# main.net
KiCad netlist of a schematic drawn in EAGLE
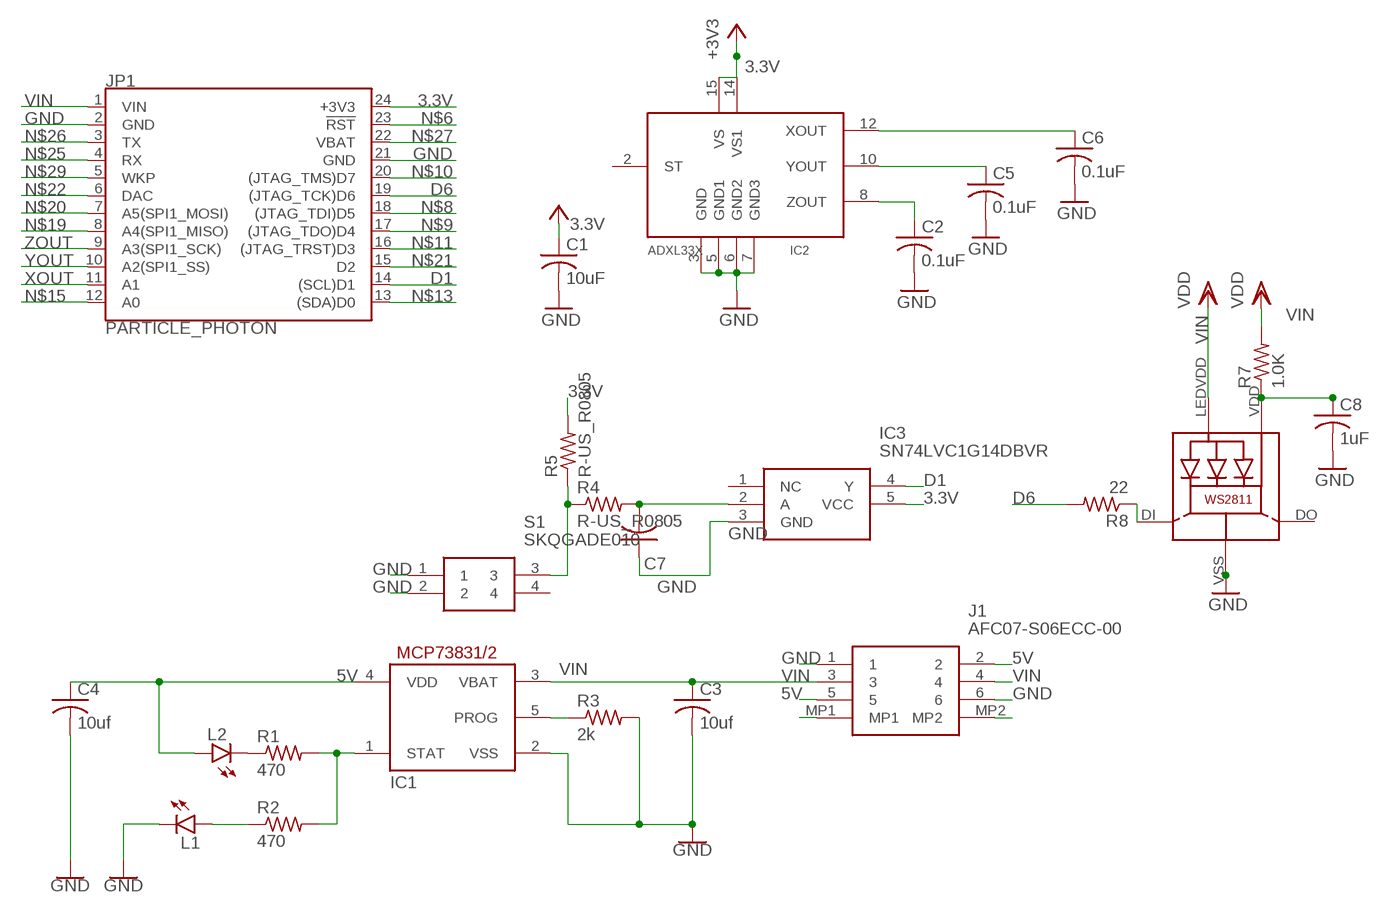
[diagram p0: schematic, sheet 1]

(export (version "E")
  (design (tool "Eeschema 10.0.6"))
  (components
    (comp (ref "C1")
      (value "10uF")
      (footprint "eagle-import:ADAFRUIT_C0805K")
      (libsource (lib "eagle-import") (part "ADAFRUIT_C-USC0805K"))
    )
    (comp (ref "C2")
      (value "0.1uF")
      (footprint "eagle-import:ADAFRUIT_C0805K")
      (libsource (lib "eagle-import") (part "ADAFRUIT_C-USC0805K"))
    )
    (comp (ref "C3")
      (value "10uf")
      (footprint "eagle-import:ADAFRUIT_C0805K")
      (libsource (lib "eagle-import") (part "ADAFRUIT_C-USC0805K"))
    )
    (comp (ref "C4")
      (value "10uf")
      (footprint "eagle-import:ADAFRUIT_C0805K")
      (libsource (lib "eagle-import") (part "ADAFRUIT_C-USC0805K"))
    )
    (comp (ref "C5")
      (value "0.1uF")
      (footprint "eagle-import:ADAFRUIT_C0805K")
      (libsource (lib "eagle-import") (part "ADAFRUIT_C-USC0805K"))
    )
    (comp (ref "C6")
      (value "0.1uF")
      (footprint "eagle-import:ADAFRUIT_C0805K")
      (libsource (lib "eagle-import") (part "ADAFRUIT_C-USC0805K"))
    )
    (comp (ref "C7")
      (value "ADAFRUIT_C-USC0805K")
      (footprint "eagle-import:ADAFRUIT_C0805K")
      (libsource (lib "eagle-import") (part "ADAFRUIT_C-USC0805K"))
    )
    (comp (ref "C8")
      (value "1uF")
      (footprint "eagle-import:ADAFRUIT_C0805K")
      (libsource (lib "eagle-import") (part "ADAFRUIT_C-USC0805K"))
    )
    (comp (ref "IC1")
      (value "MCP73831/OT")
      (footprint "eagle-import:SOT23-5L")
      (libsource (lib "eagle-import") (part "MCP73831/OT"))
    )
    (comp (ref "IC2")
      (value "ADXL33X")
      (footprint "eagle-import:16LCSP")
      (libsource (lib "eagle-import") (part "ADXL33X"))
    )
    (comp (ref "IC3")
      (value "SN74LVC1G14DBVR")
      (footprint "eagle-import:SOT95P280X145-5N")
      (fields (field (name "MOUSER_PART_NUMBER") "595-SN74LVC1G14DBVR"))
      (libsource (lib "eagle-import") (part "SN74LVC1G14DBVR"))
    )
    (comp (ref "J1")
      (value "AFC07-S06ECC-00")
      (footprint "eagle-import:AFC07S06ECC00")
      (libsource (lib "eagle-import") (part "AFC07-S06ECC-00"))
    )
    (comp (ref "JP1")
      (value "PARTICLE_PHOTON")
      (footprint "eagle-import:PARTICLE_PHOTON")
      (libsource (lib "eagle-import") (part "PARTICLE_PHOTON"))
    )
    (comp (ref "L1")
      (value "green")
      (footprint "eagle-import:FKIT-LED-1206")
      (libsource (lib "eagle-import") (part "LED-FKIT-1206"))
    )
    (comp (ref "L2")
      (value "blue")
      (footprint "eagle-import:FKIT-LED-1206")
      (libsource (lib "eagle-import") (part "LED-FKIT-1206"))
    )
    (comp (ref "LED1")
      (value "WS28115050")
      (footprint "eagle-import:WS28115050")
      (libsource (lib "eagle-import") (part "WS28115050"))
    )
    (comp (ref "R1")
      (value "470")
      (footprint "eagle-import:R0805")
      (libsource (lib "eagle-import") (part "R-US_R0805"))
    )
    (comp (ref "R2")
      (value "470")
      (footprint "eagle-import:R0805")
      (libsource (lib "eagle-import") (part "R-US_R0805"))
    )
    (comp (ref "R3")
      (value "2k")
      (footprint "eagle-import:R0805")
      (libsource (lib "eagle-import") (part "R-US_R0805"))
    )
    (comp (ref "R4")
      (value "R-US_R0805")
      (footprint "eagle-import:R0805")
      (libsource (lib "eagle-import") (part "R-US_R0805"))
    )
    (comp (ref "R5")
      (value "R-US_R0805")
      (footprint "eagle-import:R0805")
      (libsource (lib "eagle-import") (part "R-US_R0805"))
    )
    (comp (ref "R7")
      (value "1.0K")
      (footprint "eagle-import:R0805")
      (libsource (lib "eagle-import") (part "R-US_R0805"))
    )
    (comp (ref "R8")
      (value "22")
      (footprint "eagle-import:R0805")
      (libsource (lib "eagle-import") (part "R-US_R0805"))
    )
    (comp (ref "S1")
      (value "SKQGADE010")
      (footprint "eagle-import:SKQGAKE010")
      (fields (field (name "MOUSER_PART_NUMBER") "688-SKQGAD") (field (name "RS_PART_NUMBER") "7582067"))
      (libsource (lib "eagle-import") (part "SKQGADE010"))
    )
  )
  (nets
    (net (code "1") (name "+3V3") (class "Default")
      (node (ref "C1") (pin "1") (pinfunction "1_1") (pintype "passive"))
      (node (ref "IC2") (pin "14") (pinfunction "VS1_14") (pintype "power_in"))
      (node (ref "IC2") (pin "15") (pinfunction "VS_15") (pintype "power_in"))
      (node (ref "IC3") (pin "5") (pinfunction "VCC_5") (pintype "bidirectional"))
      (node (ref "JP1") (pin "24") (pinfunction "+3V3_24") (pintype "power_in"))
      (node (ref "R5") (pin "2") (pinfunction "2_2") (pintype "passive"))
    )
    (net (code "2") (name "/5V") (class "Default")
      (node (ref "C4") (pin "1") (pinfunction "1_1") (pintype "passive"))
      (node (ref "IC1") (pin "4") (pinfunction "VDD_4") (pintype "power_in"))
      (node (ref "J1") (pin "2") (pinfunction "2_2") (pintype "bidirectional"))
      (node (ref "J1") (pin "5") (pinfunction "5_5") (pintype "bidirectional"))
      (node (ref "L2") (pin "A") (pinfunction "A_A") (pintype "passive"))
    )
    (net (code "3") (name "/D1") (class "Default")
      (node (ref "IC3") (pin "4") (pinfunction "Y_4") (pintype "bidirectional"))
      (node (ref "JP1") (pin "14") (pinfunction "(SCL)D1_14") (pintype "bidirectional"))
    )
    (net (code "4") (name "/D6") (class "Default")
      (node (ref "JP1") (pin "19") (pinfunction "(JTAG_TCK)D6_19") (pintype "bidirectional"))
      (node (ref "R8") (pin "2") (pinfunction "2_2") (pintype "passive"))
    )
    (net (code "5") (name "/N$6") (class "Default")
      (node (ref "JP1") (pin "23") (pinfunction "~{RST}_23") (pintype "bidirectional"))
    )
    (net (code "6") (name "/N$8") (class "Default")
      (node (ref "JP1") (pin "18") (pinfunction "(JTAG_TDI)D5_18") (pintype "bidirectional"))
    )
    (net (code "7") (name "/N$9") (class "Default")
      (node (ref "JP1") (pin "17") (pinfunction "(JTAG_TDO)D4_17") (pintype "bidirectional"))
    )
    (net (code "8") (name "/N$10") (class "Default")
      (node (ref "JP1") (pin "20") (pinfunction "(JTAG_TMS)D7_20") (pintype "bidirectional"))
    )
    (net (code "9") (name "/N$11") (class "Default")
      (node (ref "JP1") (pin "16") (pinfunction "(JTAG_TRST)D3_16") (pintype "bidirectional"))
    )
    (net (code "10") (name "/N$13") (class "Default")
      (node (ref "JP1") (pin "13") (pinfunction "(SDA)D0_13") (pintype "bidirectional"))
    )
    (net (code "11") (name "/N$15") (class "Default")
      (node (ref "JP1") (pin "12") (pinfunction "A0_12") (pintype "bidirectional"))
    )
    (net (code "12") (name "/N$19") (class "Default")
      (node (ref "JP1") (pin "8") (pinfunction "A4(SPI1_MISO)_8") (pintype "bidirectional"))
    )
    (net (code "13") (name "/N$20") (class "Default")
      (node (ref "JP1") (pin "7") (pinfunction "A5(SPI1_MOSI)_7") (pintype "bidirectional"))
    )
    (net (code "14") (name "/N$21") (class "Default")
      (node (ref "JP1") (pin "15") (pinfunction "D2_15") (pintype "bidirectional"))
    )
    (net (code "15") (name "/N$22") (class "Default")
      (node (ref "JP1") (pin "6") (pinfunction "DAC_6") (pintype "bidirectional"))
    )
    (net (code "16") (name "/N$25") (class "Default")
      (node (ref "JP1") (pin "4") (pinfunction "RX_4") (pintype "bidirectional"))
    )
    (net (code "17") (name "/N$26") (class "Default")
      (node (ref "JP1") (pin "3") (pinfunction "TX_3") (pintype "bidirectional"))
    )
    (net (code "18") (name "/N$27") (class "Default")
      (node (ref "JP1") (pin "22") (pinfunction "VBAT_22") (pintype "power_in"))
    )
    (net (code "19") (name "/N$29") (class "Default")
      (node (ref "JP1") (pin "5") (pinfunction "WKP_5") (pintype "bidirectional"))
    )
    (net (code "20") (name "/XOUT") (class "Default")
      (node (ref "C6") (pin "1") (pinfunction "1_1") (pintype "passive"))
      (node (ref "IC2") (pin "12") (pinfunction "XOUT_12") (pintype "output"))
      (node (ref "JP1") (pin "11") (pinfunction "A1_11") (pintype "bidirectional"))
    )
    (net (code "21") (name "/YOUT") (class "Default")
      (node (ref "C5") (pin "1") (pinfunction "1_1") (pintype "passive"))
      (node (ref "IC2") (pin "10") (pinfunction "YOUT_10") (pintype "output"))
      (node (ref "JP1") (pin "10") (pinfunction "A2(SPI1_SS)_10") (pintype "bidirectional"))
    )
    (net (code "22") (name "/ZOUT") (class "Default")
      (node (ref "C2") (pin "1") (pinfunction "1_1") (pintype "passive"))
      (node (ref "IC2") (pin "8") (pinfunction "ZOUT_8") (pintype "output"))
      (node (ref "JP1") (pin "9") (pinfunction "A3(SPI1_SCK)_9") (pintype "bidirectional"))
    )
    (net (code "23") (name "GND") (class "Default")
      (node (ref "C1") (pin "2") (pinfunction "2_2") (pintype "passive"))
      (node (ref "C2") (pin "2") (pinfunction "2_2") (pintype "passive"))
      (node (ref "C3") (pin "2") (pinfunction "2_2") (pintype "passive"))
      (node (ref "C4") (pin "2") (pinfunction "2_2") (pintype "passive"))
      (node (ref "C5") (pin "2") (pinfunction "2_2") (pintype "passive"))
      (node (ref "C6") (pin "2") (pinfunction "2_2") (pintype "passive"))
      (node (ref "C7") (pin "1") (pinfunction "1_1") (pintype "passive"))
      (node (ref "C8") (pin "2") (pinfunction "2_2") (pintype "passive"))
      (node (ref "IC1") (pin "2") (pinfunction "VSS_2") (pintype "power_in"))
      (node (ref "IC2") (pin "3") (pinfunction "GND_3") (pintype "power_in"))
      (node (ref "IC2") (pin "5") (pinfunction "GND1_5") (pintype "power_in"))
      (node (ref "IC2") (pin "6") (pinfunction "GND2_6") (pintype "power_in"))
      (node (ref "IC2") (pin "7") (pinfunction "GND3_7") (pintype "power_in"))
      (node (ref "IC3") (pin "3") (pinfunction "GND_3") (pintype "bidirectional"))
      (node (ref "J1") (pin "1") (pinfunction "1_1") (pintype "bidirectional"))
      (node (ref "J1") (pin "6") (pinfunction "6_6") (pintype "bidirectional"))
      (node (ref "JP1") (pin "2") (pinfunction "GND_2") (pintype "power_in"))
      (node (ref "JP1") (pin "21") (pinfunction "GND_21") (pintype "power_in"))
      (node (ref "L1") (pin "C") (pinfunction "C_C") (pintype "passive"))
      (node (ref "LED1") (pin "VSS") (pinfunction "GND_VSS") (pintype "power_in"))
      (node (ref "R3") (pin "2") (pinfunction "2_2") (pintype "passive"))
      (node (ref "S1") (pin "1") (pinfunction "1_1") (pintype "bidirectional"))
      (node (ref "S1") (pin "2") (pinfunction "2_2") (pintype "bidirectional"))
    )
    (net (code "24") (name "Net-(C8-Pad1)") (class "Default")
      (node (ref "C8") (pin "1") (pinfunction "1_1") (pintype "passive"))
      (node (ref "LED1") (pin "VDD") (pinfunction "VDD_VDD") (pintype "power_in"))
      (node (ref "R7") (pin "1") (pinfunction "1_1") (pintype "passive"))
    )
    (net (code "25") (name "Net-(IC1-PROG)") (class "Default")
      (node (ref "IC1") (pin "5") (pinfunction "PROG_5") (pintype "input"))
      (node (ref "R3") (pin "1") (pinfunction "1_1") (pintype "passive"))
    )
    (net (code "26") (name "Net-(IC1-STAT)") (class "Default")
      (node (ref "IC1") (pin "1") (pinfunction "STAT_1") (pintype "output"))
      (node (ref "R1") (pin "2") (pinfunction "2_2") (pintype "passive"))
      (node (ref "R2") (pin "2") (pinfunction "2_2") (pintype "passive"))
    )
    (net (code "27") (name "Net-(IC3-A)") (class "Default")
      (node (ref "C7") (pin "2") (pinfunction "2_2") (pintype "passive"))
      (node (ref "IC3") (pin "2") (pinfunction "A_2") (pintype "bidirectional"))
      (node (ref "R4") (pin "2") (pinfunction "2_2") (pintype "passive"))
    )
    (net (code "28") (name "Net-(L1-PadA)") (class "Default")
      (node (ref "L1") (pin "A") (pinfunction "A_A") (pintype "passive"))
      (node (ref "R2") (pin "1") (pinfunction "1_1") (pintype "passive"))
    )
    (net (code "29") (name "Net-(L2-PadC)") (class "Default")
      (node (ref "L2") (pin "C") (pinfunction "C_C") (pintype "passive"))
      (node (ref "R1") (pin "1") (pinfunction "1_1") (pintype "passive"))
    )
    (net (code "30") (name "Net-(LED1-PadDI)") (class "Default")
      (node (ref "LED1") (pin "DI") (pinfunction "DI_DI") (pintype "input"))
      (node (ref "R8") (pin "1") (pinfunction "1_1") (pintype "passive"))
    )
    (net (code "31") (name "Net-(R4-Pad1)") (class "Default")
      (node (ref "R4") (pin "1") (pinfunction "1_1") (pintype "passive"))
      (node (ref "R5") (pin "1") (pinfunction "1_1") (pintype "passive"))
      (node (ref "S1") (pin "3") (pinfunction "3_3") (pintype "bidirectional"))
    )
    (net (code "32") (name "VDD") (class "Default")
      (node (ref "C3") (pin "1") (pinfunction "1_1") (pintype "passive"))
      (node (ref "IC1") (pin "3") (pinfunction "VBAT_3") (pintype "bidirectional"))
      (node (ref "J1") (pin "3") (pinfunction "3_3") (pintype "bidirectional"))
      (node (ref "J1") (pin "4") (pinfunction "4_4") (pintype "bidirectional"))
      (node (ref "JP1") (pin "1") (pinfunction "VIN_1") (pintype "power_in"))
      (node (ref "LED1") (pin "LEDVDD") (pinfunction "LEDVDD_LEDVDD") (pintype "power_in"))
      (node (ref "R7") (pin "2") (pinfunction "2_2") (pintype "passive"))
    )
    (net (code "33") (name "unconnected-(IC2-ST-Pad2)") (class "Default")
      (node (ref "IC2") (pin "2") (pinfunction "ST_2") (pintype "input"))
    )
    (net (code "34") (name "unconnected-(IC3-NC-Pad1)") (class "Default")
      (node (ref "IC3") (pin "1") (pinfunction "NC_1") (pintype "no_connect"))
    )
    (net (code "35") (name "unconnected-(J1-PadMP1)") (class "Default")
      (node (ref "J1") (pin "MP1") (pinfunction "MP1_MP1") (pintype "bidirectional"))
    )
    (net (code "36") (name "unconnected-(J1-PadMP2)") (class "Default")
      (node (ref "J1") (pin "MP2") (pinfunction "MP2_MP2") (pintype "bidirectional"))
    )
    (net (code "37") (name "unconnected-(LED1-PadDO)") (class "Default")
      (node (ref "LED1") (pin "DO") (pinfunction "DO_DO") (pintype "output"))
    )
    (net (code "38") (name "unconnected-(S1-Pad4)") (class "Default")
      (node (ref "S1") (pin "4") (pinfunction "4_4") (pintype "bidirectional"))
    )
  )
)
